# design_schematic.net
KiCad netlist of a schematic drawn in EasyEDA
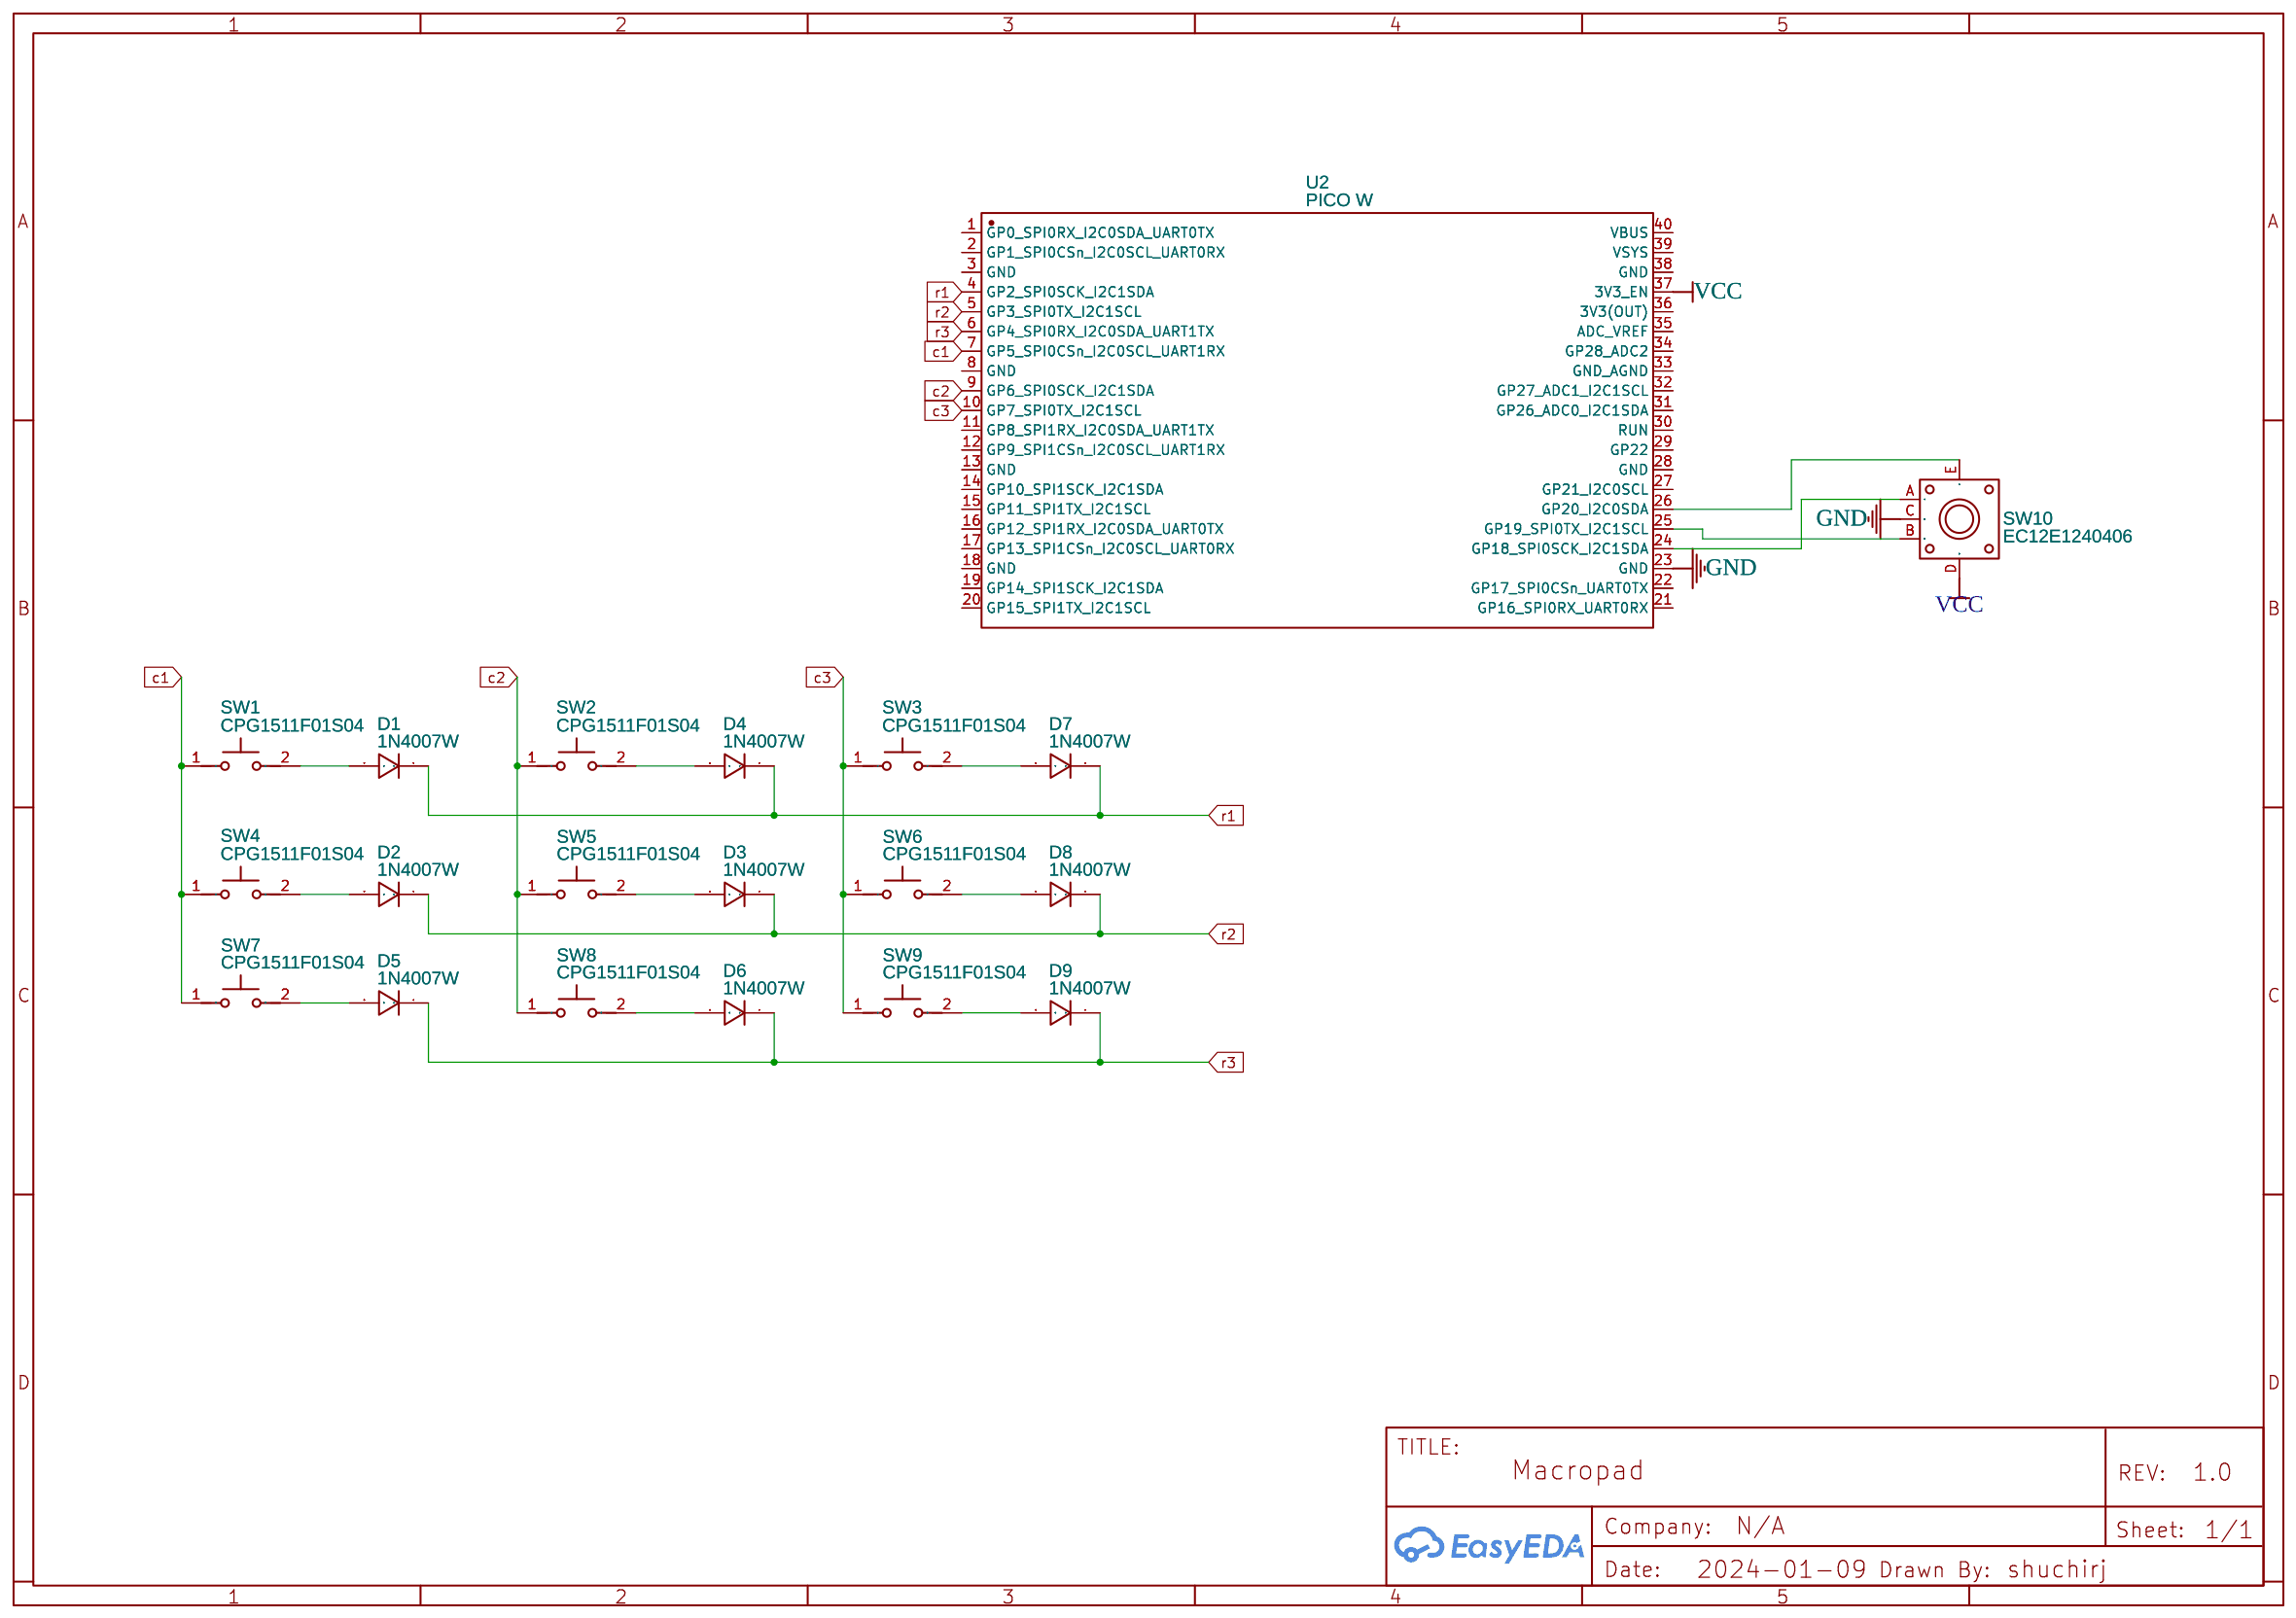
[diagram p0: schematic sheet]

(export (version "E")
  (design (tool "Eeschema 10.0.6"))
  (components
    (comp (ref "D1")
      (value "1N4007W")
      (fields (field (name "Manufacturer") "BLUE ROCKET"))
      (libsource (lib "") (part "1N4007W"))
    )
    (comp (ref "D2")
      (value "1N4007W")
      (fields (field (name "Manufacturer") "BLUE ROCKET"))
      (libsource (lib "") (part "1N4007W"))
    )
    (comp (ref "D3")
      (value "1N4007W")
      (fields (field (name "Manufacturer") "BLUE ROCKET"))
      (libsource (lib "") (part "1N4007W"))
    )
    (comp (ref "D4")
      (value "1N4007W")
      (fields (field (name "Manufacturer") "BLUE ROCKET"))
      (libsource (lib "") (part "1N4007W"))
    )
    (comp (ref "D5")
      (value "1N4007W")
      (fields (field (name "Manufacturer") "BLUE ROCKET"))
      (libsource (lib "") (part "1N4007W"))
    )
    (comp (ref "D6")
      (value "1N4007W")
      (fields (field (name "Manufacturer") "BLUE ROCKET"))
      (libsource (lib "") (part "1N4007W"))
    )
    (comp (ref "D7")
      (value "1N4007W")
      (fields (field (name "Manufacturer") "BLUE ROCKET"))
      (libsource (lib "") (part "1N4007W"))
    )
    (comp (ref "D8")
      (value "1N4007W")
      (fields (field (name "Manufacturer") "BLUE ROCKET"))
      (libsource (lib "") (part "1N4007W"))
    )
    (comp (ref "D9")
      (value "1N4007W")
      (fields (field (name "Manufacturer") "BLUE ROCKET"))
      (libsource (lib "") (part "1N4007W"))
    )
    (comp (ref "SW1")
      (value "CPG1511F01S04")
      (fields (field (name "Manufacturer") "Kailh"))
      (libsource (lib "") (part "CPG1511F01S04"))
    )
    (comp (ref "SW2")
      (value "CPG1511F01S04")
      (fields (field (name "Manufacturer") "Kailh"))
      (libsource (lib "") (part "CPG1511F01S04"))
    )
    (comp (ref "SW3")
      (value "CPG1511F01S04")
      (fields (field (name "Manufacturer") "Kailh"))
      (libsource (lib "") (part "CPG1511F01S04"))
    )
    (comp (ref "SW4")
      (value "CPG1511F01S04")
      (fields (field (name "Manufacturer") "Kailh"))
      (libsource (lib "") (part "CPG1511F01S04"))
    )
    (comp (ref "SW5")
      (value "CPG1511F01S04")
      (fields (field (name "Manufacturer") "Kailh"))
      (libsource (lib "") (part "CPG1511F01S04"))
    )
    (comp (ref "SW6")
      (value "CPG1511F01S04")
      (fields (field (name "Manufacturer") "Kailh"))
      (libsource (lib "") (part "CPG1511F01S04"))
    )
    (comp (ref "SW7")
      (value "CPG1511F01S04")
      (fields (field (name "Manufacturer") "Kailh"))
      (libsource (lib "") (part "CPG1511F01S04"))
    )
    (comp (ref "SW8")
      (value "CPG1511F01S04")
      (fields (field (name "Manufacturer") "Kailh"))
      (libsource (lib "") (part "CPG1511F01S04"))
    )
    (comp (ref "SW9")
      (value "CPG1511F01S04")
      (fields (field (name "Manufacturer") "Kailh"))
      (libsource (lib "") (part "CPG1511F01S04"))
    )
    (comp (ref "SW10")
      (value "EC12E1240406")
      (fields (field (name "Manufacturer") "ALPS Electric"))
      (libsource (lib "") (part "EC12E1240406"))
    )
    (comp (ref "U2")
      (value "PICO W")
      (fields (field (name "Manufacturer") "Raspberry Pi(树莓派)"))
      (libsource (lib "") (part "PICO W"))
    )
  )
  (nets
    (net (code "1") (name "GND") (class "Default")
      (node (ref "SW10") (pin "C") (pinfunction "C_C") (pintype "unspecified"))
      (node (ref "U2") (pin "23") (pinfunction "GND_23") (pintype "unspecified"))
    )
    (net (code "2") (name "Net-(D1-Pad2)") (class "Default")
      (node (ref "D1") (pin "2") (pinfunction "2_2") (pintype "unspecified"))
      (node (ref "SW1") (pin "2") (pinfunction "2_2") (pintype "unspecified"))
    )
    (net (code "3") (name "Net-(D2-Pad2)") (class "Default")
      (node (ref "D2") (pin "2") (pinfunction "2_2") (pintype "unspecified"))
      (node (ref "SW4") (pin "2") (pinfunction "2_2") (pintype "unspecified"))
    )
    (net (code "4") (name "Net-(D3-Pad2)") (class "Default")
      (node (ref "D3") (pin "2") (pinfunction "2_2") (pintype "unspecified"))
      (node (ref "SW5") (pin "2") (pinfunction "2_2") (pintype "unspecified"))
    )
    (net (code "5") (name "Net-(D4-Pad2)") (class "Default")
      (node (ref "D4") (pin "2") (pinfunction "2_2") (pintype "unspecified"))
      (node (ref "SW2") (pin "2") (pinfunction "2_2") (pintype "unspecified"))
    )
    (net (code "6") (name "Net-(D5-Pad2)") (class "Default")
      (node (ref "D5") (pin "2") (pinfunction "2_2") (pintype "unspecified"))
      (node (ref "SW7") (pin "2") (pinfunction "2_2") (pintype "unspecified"))
    )
    (net (code "7") (name "Net-(D6-Pad2)") (class "Default")
      (node (ref "D6") (pin "2") (pinfunction "2_2") (pintype "unspecified"))
      (node (ref "SW8") (pin "2") (pinfunction "2_2") (pintype "unspecified"))
    )
    (net (code "8") (name "Net-(D7-Pad2)") (class "Default")
      (node (ref "D7") (pin "2") (pinfunction "2_2") (pintype "unspecified"))
      (node (ref "SW3") (pin "2") (pinfunction "2_2") (pintype "unspecified"))
    )
    (net (code "9") (name "Net-(D8-Pad2)") (class "Default")
      (node (ref "D8") (pin "2") (pinfunction "2_2") (pintype "unspecified"))
      (node (ref "SW6") (pin "2") (pinfunction "2_2") (pintype "unspecified"))
    )
    (net (code "10") (name "Net-(D9-Pad2)") (class "Default")
      (node (ref "D9") (pin "2") (pinfunction "2_2") (pintype "unspecified"))
      (node (ref "SW9") (pin "2") (pinfunction "2_2") (pintype "unspecified"))
    )
    (net (code "11") (name "Net-(U2-GP18_SPI0SCK_I2C1SDA)") (class "Default")
      (node (ref "SW10") (pin "A") (pinfunction "A_A") (pintype "unspecified"))
      (node (ref "U2") (pin "24") (pinfunction "GP18_SPI0SCK_I2C1SDA_24") (pintype "unspecified"))
    )
    (net (code "12") (name "Net-(U2-GP19_SPI0TX_I2C1SCL)") (class "Default")
      (node (ref "SW10") (pin "B") (pinfunction "B_B") (pintype "unspecified"))
      (node (ref "U2") (pin "25") (pinfunction "GP19_SPI0TX_I2C1SCL_25") (pintype "unspecified"))
    )
    (net (code "13") (name "Net-(U2-GP20_I2C0SDA)") (class "Default")
      (node (ref "SW10") (pin "E") (pinfunction "E_E") (pintype "unspecified"))
      (node (ref "U2") (pin "26") (pinfunction "GP20_I2C0SDA_26") (pintype "unspecified"))
    )
    (net (code "14") (name "VCC") (class "Default")
      (node (ref "SW10") (pin "D") (pinfunction "D_D") (pintype "unspecified"))
      (node (ref "U2") (pin "37") (pinfunction "3V3_EN_37") (pintype "unspecified"))
    )
    (net (code "15") (name "c1") (class "Default")
      (node (ref "SW1") (pin "1") (pinfunction "1_1") (pintype "unspecified"))
      (node (ref "SW4") (pin "1") (pinfunction "1_1") (pintype "unspecified"))
      (node (ref "SW7") (pin "1") (pinfunction "1_1") (pintype "unspecified"))
      (node (ref "U2") (pin "7") (pinfunction "GP5_SPI0CSn_I2C0SCL_UART1RX_7") (pintype "unspecified"))
    )
    (net (code "16") (name "c2") (class "Default")
      (node (ref "SW2") (pin "1") (pinfunction "1_1") (pintype "unspecified"))
      (node (ref "SW5") (pin "1") (pinfunction "1_1") (pintype "unspecified"))
      (node (ref "SW8") (pin "1") (pinfunction "1_1") (pintype "unspecified"))
      (node (ref "U2") (pin "9") (pinfunction "GP6_SPI0SCK_I2C1SDA_9") (pintype "unspecified"))
    )
    (net (code "17") (name "c3") (class "Default")
      (node (ref "SW3") (pin "1") (pinfunction "1_1") (pintype "unspecified"))
      (node (ref "SW6") (pin "1") (pinfunction "1_1") (pintype "unspecified"))
      (node (ref "SW9") (pin "1") (pinfunction "1_1") (pintype "unspecified"))
      (node (ref "U2") (pin "10") (pinfunction "GP7_SPI0TX_I2C1SCL_10") (pintype "unspecified"))
    )
    (net (code "18") (name "r1") (class "Default")
      (node (ref "D1") (pin "1") (pinfunction "1_1") (pintype "unspecified"))
      (node (ref "D4") (pin "1") (pinfunction "1_1") (pintype "unspecified"))
      (node (ref "D7") (pin "1") (pinfunction "1_1") (pintype "unspecified"))
      (node (ref "U2") (pin "4") (pinfunction "GP2_SPI0SCK_I2C1SDA_4") (pintype "unspecified"))
    )
    (net (code "19") (name "r2") (class "Default")
      (node (ref "D2") (pin "1") (pinfunction "1_1") (pintype "unspecified"))
      (node (ref "D3") (pin "1") (pinfunction "1_1") (pintype "unspecified"))
      (node (ref "D8") (pin "1") (pinfunction "1_1") (pintype "unspecified"))
      (node (ref "U2") (pin "5") (pinfunction "GP3_SPI0TX_I2C1SCL_5") (pintype "unspecified"))
    )
    (net (code "20") (name "r3") (class "Default")
      (node (ref "D5") (pin "1") (pinfunction "1_1") (pintype "unspecified"))
      (node (ref "D6") (pin "1") (pinfunction "1_1") (pintype "unspecified"))
      (node (ref "D9") (pin "1") (pinfunction "1_1") (pintype "unspecified"))
      (node (ref "U2") (pin "6") (pinfunction "GP4_SPI0RX_I2C0SDA_UART1TX_6") (pintype "unspecified"))
    )
    (net (code "21") (name "unconnected-(U2-3V3(OUT)-Pad36)") (class "Default")
      (node (ref "U2") (pin "36") (pinfunction "3V3(OUT)_36") (pintype "unspecified"))
    )
    (net (code "22") (name "unconnected-(U2-ADC_VREF-Pad35)") (class "Default")
      (node (ref "U2") (pin "35") (pinfunction "ADC_VREF_35") (pintype "unspecified"))
    )
    (net (code "23") (name "unconnected-(U2-GND-Pad3)") (class "Default")
      (node (ref "U2") (pin "3") (pinfunction "GND_3") (pintype "unspecified"))
    )
    (net (code "24") (name "unconnected-(U2-GND-Pad8)") (class "Default")
      (node (ref "U2") (pin "8") (pinfunction "GND_8") (pintype "unspecified"))
    )
    (net (code "25") (name "unconnected-(U2-GND-Pad13)") (class "Default")
      (node (ref "U2") (pin "13") (pinfunction "GND_13") (pintype "unspecified"))
    )
    (net (code "26") (name "unconnected-(U2-GND-Pad18)") (class "Default")
      (node (ref "U2") (pin "18") (pinfunction "GND_18") (pintype "unspecified"))
    )
    (net (code "27") (name "unconnected-(U2-GND-Pad28)") (class "Default")
      (node (ref "U2") (pin "28") (pinfunction "GND_28") (pintype "unspecified"))
    )
    (net (code "28") (name "unconnected-(U2-GND-Pad38)") (class "Default")
      (node (ref "U2") (pin "38") (pinfunction "GND_38") (pintype "unspecified"))
    )
    (net (code "29") (name "unconnected-(U2-GND_AGND-Pad33)") (class "Default")
      (node (ref "U2") (pin "33") (pinfunction "GND_AGND_33") (pintype "unspecified"))
    )
    (net (code "30") (name "unconnected-(U2-GP0_SPI0RX_I2C0SDA_UART0TX-Pad1)") (class "Default")
      (node (ref "U2") (pin "1") (pinfunction "GP0_SPI0RX_I2C0SDA_UART0TX_1") (pintype "unspecified"))
    )
    (net (code "31") (name "unconnected-(U2-GP1_SPI0CSn_I2C0SCL_UART0RX-Pad2)") (class "Default")
      (node (ref "U2") (pin "2") (pinfunction "GP1_SPI0CSn_I2C0SCL_UART0RX_2") (pintype "unspecified"))
    )
    (net (code "32") (name "unconnected-(U2-GP8_SPI1RX_I2C0SDA_UART1TX-Pad11)") (class "Default")
      (node (ref "U2") (pin "11") (pinfunction "GP8_SPI1RX_I2C0SDA_UART1TX_11") (pintype "unspecified"))
    )
    (net (code "33") (name "unconnected-(U2-GP9_SPI1CSn_I2C0SCL_UART1RX-Pad12)") (class "Default")
      (node (ref "U2") (pin "12") (pinfunction "GP9_SPI1CSn_I2C0SCL_UART1RX_12") (pintype "unspecified"))
    )
    (net (code "34") (name "unconnected-(U2-GP10_SPI1SCK_I2C1SDA-Pad14)") (class "Default")
      (node (ref "U2") (pin "14") (pinfunction "GP10_SPI1SCK_I2C1SDA_14") (pintype "unspecified"))
    )
    (net (code "35") (name "unconnected-(U2-GP11_SPI1TX_I2C1SCL-Pad15)") (class "Default")
      (node (ref "U2") (pin "15") (pinfunction "GP11_SPI1TX_I2C1SCL_15") (pintype "unspecified"))
    )
    (net (code "36") (name "unconnected-(U2-GP12_SPI1RX_I2C0SDA_UART0TX-Pad16)") (class "Default")
      (node (ref "U2") (pin "16") (pinfunction "GP12_SPI1RX_I2C0SDA_UART0TX_16") (pintype "unspecified"))
    )
    (net (code "37") (name "unconnected-(U2-GP13_SPI1CSn_I2C0SCL_UART0RX-Pad17)") (class "Default")
      (node (ref "U2") (pin "17") (pinfunction "GP13_SPI1CSn_I2C0SCL_UART0RX_17") (pintype "unspecified"))
    )
    (net (code "38") (name "unconnected-(U2-GP14_SPI1SCK_I2C1SDA-Pad19)") (class "Default")
      (node (ref "U2") (pin "19") (pinfunction "GP14_SPI1SCK_I2C1SDA_19") (pintype "unspecified"))
    )
    (net (code "39") (name "unconnected-(U2-GP15_SPI1TX_I2C1SCL-Pad20)") (class "Default")
      (node (ref "U2") (pin "20") (pinfunction "GP15_SPI1TX_I2C1SCL_20") (pintype "unspecified"))
    )
    (net (code "40") (name "unconnected-(U2-GP16_SPI0RX_UART0RX-Pad21)") (class "Default")
      (node (ref "U2") (pin "21") (pinfunction "GP16_SPI0RX_UART0RX_21") (pintype "unspecified"))
    )
    (net (code "41") (name "unconnected-(U2-GP17_SPI0CSn_UART0TX-Pad22)") (class "Default")
      (node (ref "U2") (pin "22") (pinfunction "GP17_SPI0CSn_UART0TX_22") (pintype "unspecified"))
    )
    (net (code "42") (name "unconnected-(U2-GP21_I2C0SCL-Pad27)") (class "Default")
      (node (ref "U2") (pin "27") (pinfunction "GP21_I2C0SCL_27") (pintype "unspecified"))
    )
    (net (code "43") (name "unconnected-(U2-GP22-Pad29)") (class "Default")
      (node (ref "U2") (pin "29") (pinfunction "GP22_29") (pintype "unspecified"))
    )
    (net (code "44") (name "unconnected-(U2-GP26_ADC0_I2C1SDA-Pad31)") (class "Default")
      (node (ref "U2") (pin "31") (pinfunction "GP26_ADC0_I2C1SDA_31") (pintype "unspecified"))
    )
    (net (code "45") (name "unconnected-(U2-GP27_ADC1_I2C1SCL-Pad32)") (class "Default")
      (node (ref "U2") (pin "32") (pinfunction "GP27_ADC1_I2C1SCL_32") (pintype "unspecified"))
    )
    (net (code "46") (name "unconnected-(U2-GP28_ADC2-Pad34)") (class "Default")
      (node (ref "U2") (pin "34") (pinfunction "GP28_ADC2_34") (pintype "unspecified"))
    )
    (net (code "47") (name "unconnected-(U2-RUN-Pad30)") (class "Default")
      (node (ref "U2") (pin "30") (pinfunction "RUN_30") (pintype "unspecified"))
    )
    (net (code "48") (name "unconnected-(U2-VBUS-Pad40)") (class "Default")
      (node (ref "U2") (pin "40") (pinfunction "VBUS_40") (pintype "unspecified"))
    )
    (net (code "49") (name "unconnected-(U2-VSYS-Pad39)") (class "Default")
      (node (ref "U2") (pin "39") (pinfunction "VSYS_39") (pintype "unspecified"))
    )
  )
)
